# Panel.net
KiCad netlist of a schematic drawn in EAGLE
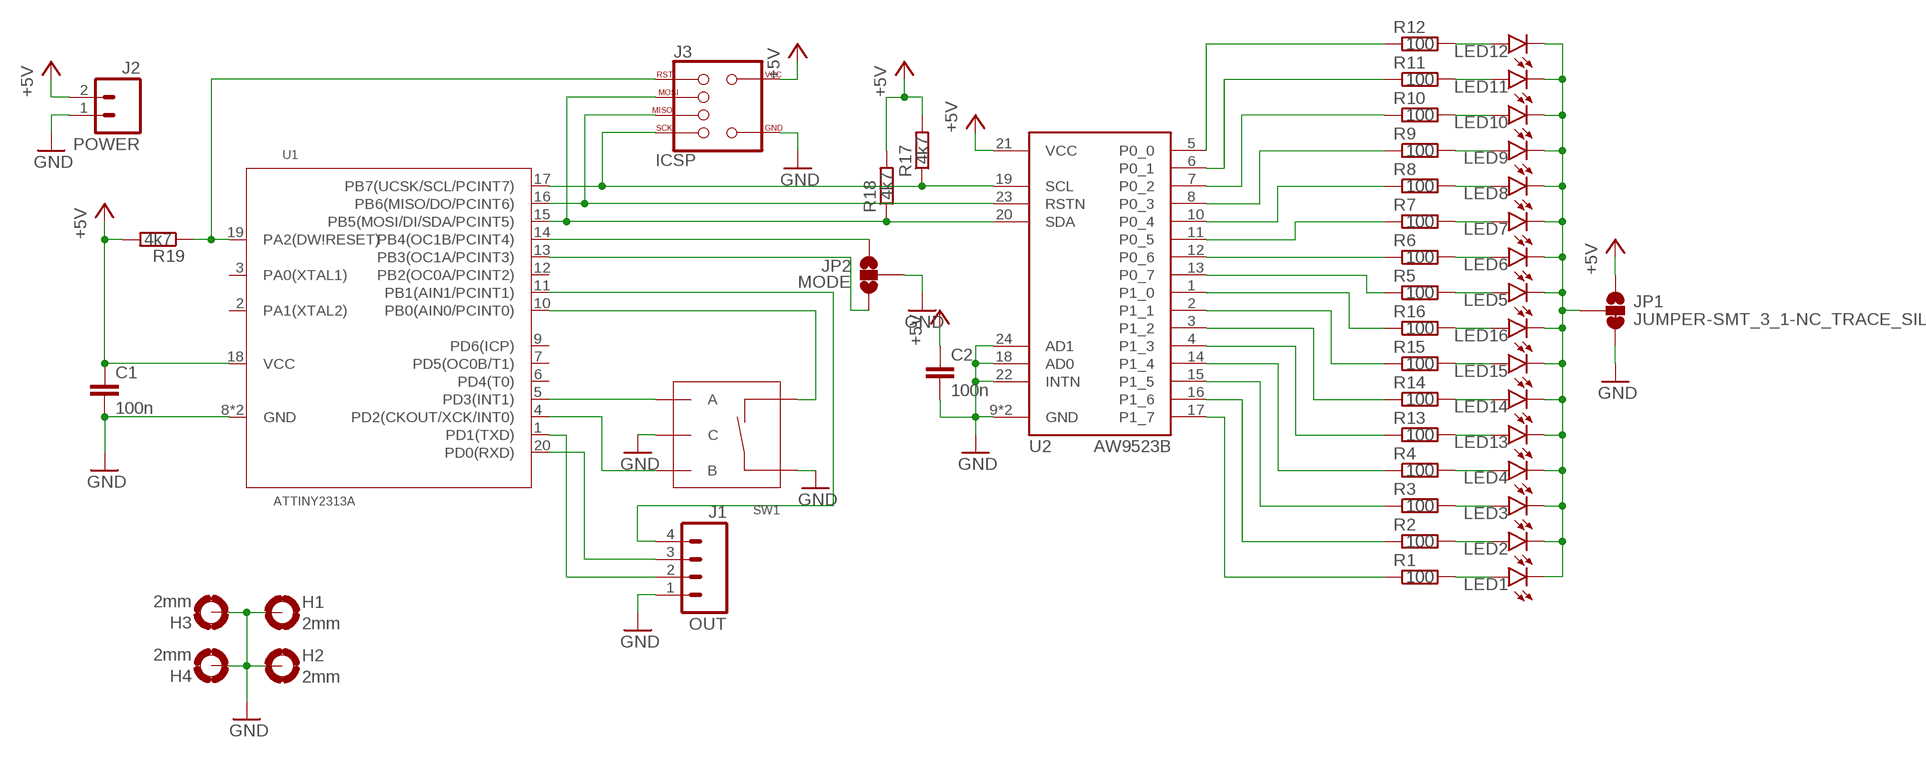
[diagram p0: schematic, sheet 2]
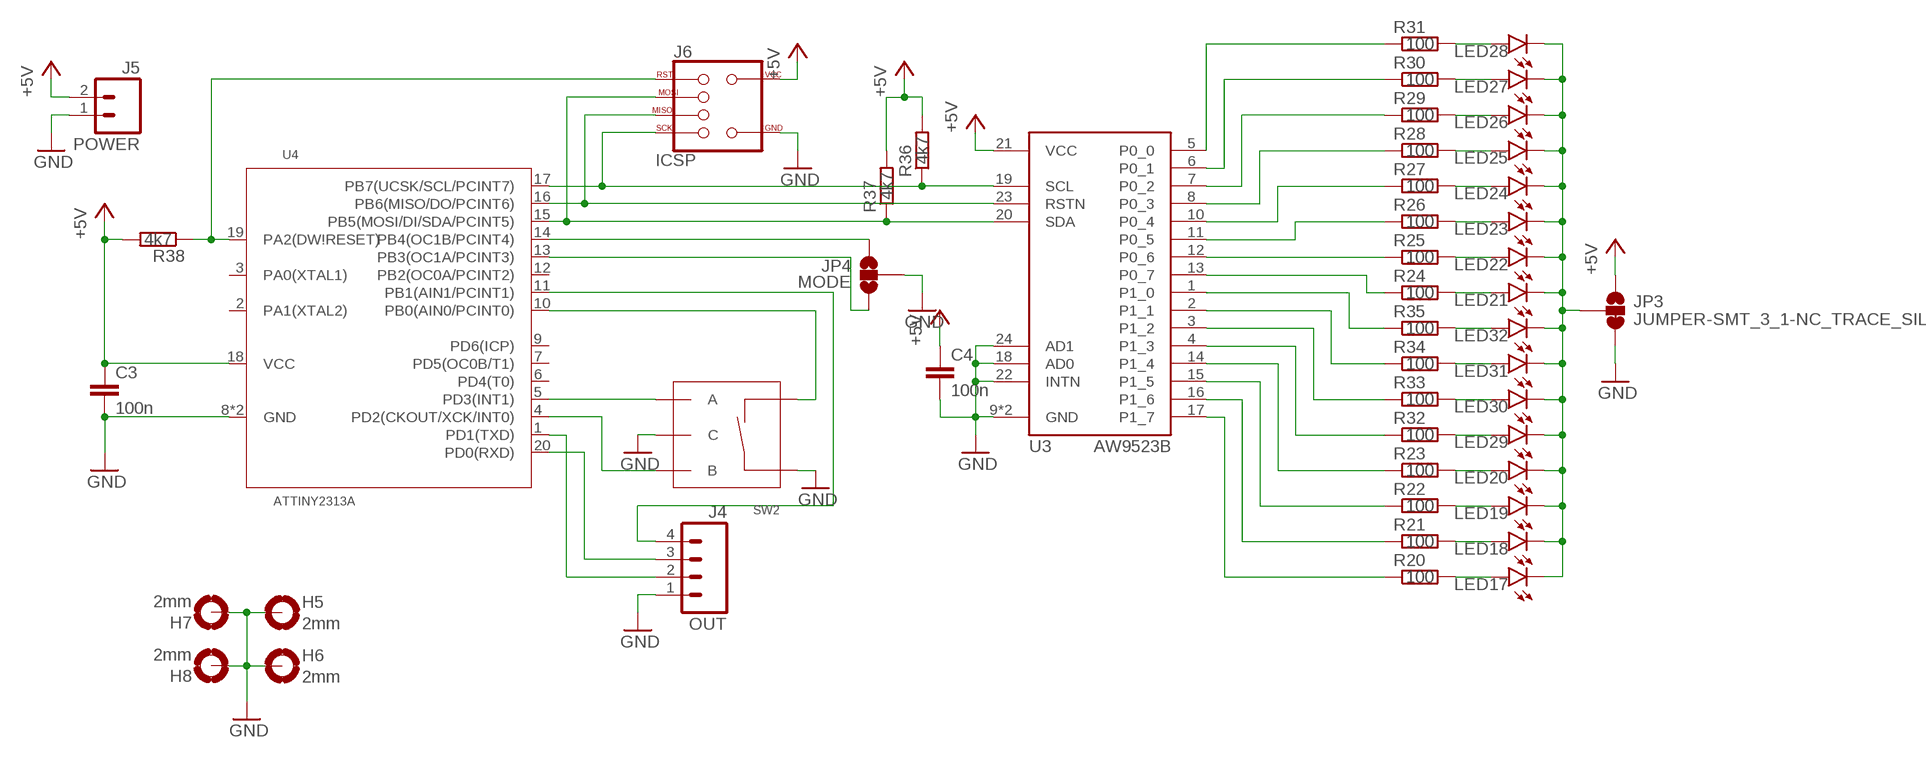
[diagram p1: schematic, sheet 3]

(export (version "E")
  (design (tool "Eeschema 10.0.6"))
  (components
    (comp (ref "C3")
      (value "100n")
      (footprint "eagle-import:C0402")
      (libsource (lib "eagle-import") (part "C-EUC0402"))
    )
    (comp (ref "C4")
      (value "100n")
      (footprint "eagle-import:C0402")
      (libsource (lib "eagle-import") (part "C-EUC0402"))
    )
    (comp (ref "H5")
      (value "2mm")
      (footprint "eagle-import:2,0-PAD")
      (libsource (lib "eagle-import") (part "MOUNT-PAD2MM"))
    )
    (comp (ref "H6")
      (value "2mm")
      (footprint "eagle-import:2,0-PAD")
      (libsource (lib "eagle-import") (part "MOUNT-PAD2MM"))
    )
    (comp (ref "H7")
      (value "2mm")
      (footprint "eagle-import:2,0-PAD")
      (libsource (lib "eagle-import") (part "MOUNT-PAD2MM"))
    )
    (comp (ref "H8")
      (value "2mm")
      (footprint "eagle-import:2,0-PAD")
      (libsource (lib "eagle-import") (part "MOUNT-PAD2MM"))
    )
    (comp (ref "J4")
      (value "OUT")
      (footprint "eagle-import:JST-4-PTH-VERT")
      (libsource (lib "eagle-import") (part "JST-XH4"))
    )
    (comp (ref "J5")
      (value "POWER")
      (footprint "eagle-import:JST-2-PTH-VERT")
      (libsource (lib "eagle-import") (part "JST-XH2"))
    )
    (comp (ref "J6")
      (value "ICSP")
      (footprint "eagle-import:MINI-ISP-LABELS")
      (libsource (lib "eagle-import") (part "MINI-ISP-LABELS"))
    )
    (comp (ref "JP3")
      (value "JUMPER-SMT_3_1-NC_TRACE_SILK")
      (footprint "eagle-import:SMT-JUMPER_3_1-NC_TRACE_SILK")
      (libsource (lib "eagle-import") (part "JUMPER-SMT_3_1-NC_TRACE_SILK"))
    )
    (comp (ref "JP4")
      (value "MODE")
      (footprint "eagle-import:SMT-JUMPER_3_NO_SILK")
      (libsource (lib "eagle-import") (part "JUMPER-SMT_3_NO_SILK"))
    )
    (comp (ref "LED17")
      (value "LED-BLUE0603")
      (footprint "eagle-import:0603-BLUE")
      (libsource (lib "eagle-import") (part "LED-BLUE0603"))
    )
    (comp (ref "LED18")
      (value "LED-BLUE0603")
      (footprint "eagle-import:0603-BLUE")
      (libsource (lib "eagle-import") (part "LED-BLUE0603"))
    )
    (comp (ref "LED19")
      (value "LED-BLUE0603")
      (footprint "eagle-import:0603-BLUE")
      (libsource (lib "eagle-import") (part "LED-BLUE0603"))
    )
    (comp (ref "LED20")
      (value "LED-BLUE0603")
      (footprint "eagle-import:0603-BLUE")
      (libsource (lib "eagle-import") (part "LED-BLUE0603"))
    )
    (comp (ref "LED21")
      (value "LED-BLUE0603")
      (footprint "eagle-import:0603-BLUE")
      (libsource (lib "eagle-import") (part "LED-BLUE0603"))
    )
    (comp (ref "LED22")
      (value "LED-BLUE0603")
      (footprint "eagle-import:0603-BLUE")
      (libsource (lib "eagle-import") (part "LED-BLUE0603"))
    )
    (comp (ref "LED23")
      (value "LED-BLUE0603")
      (footprint "eagle-import:0603-BLUE")
      (libsource (lib "eagle-import") (part "LED-BLUE0603"))
    )
    (comp (ref "LED24")
      (value "LED-BLUE0603")
      (footprint "eagle-import:0603-BLUE")
      (libsource (lib "eagle-import") (part "LED-BLUE0603"))
    )
    (comp (ref "LED25")
      (value "LED-BLUE0603")
      (footprint "eagle-import:0603-BLUE")
      (libsource (lib "eagle-import") (part "LED-BLUE0603"))
    )
    (comp (ref "LED26")
      (value "LED-BLUE0603")
      (footprint "eagle-import:0603-BLUE")
      (libsource (lib "eagle-import") (part "LED-BLUE0603"))
    )
    (comp (ref "LED27")
      (value "LED-BLUE0603")
      (footprint "eagle-import:0603-BLUE")
      (libsource (lib "eagle-import") (part "LED-BLUE0603"))
    )
    (comp (ref "LED28")
      (value "LED-BLUE0603")
      (footprint "eagle-import:0603-BLUE")
      (libsource (lib "eagle-import") (part "LED-BLUE0603"))
    )
    (comp (ref "LED29")
      (value "LED-BLUE0603")
      (footprint "eagle-import:0603-BLUE")
      (libsource (lib "eagle-import") (part "LED-BLUE0603"))
    )
    (comp (ref "LED30")
      (value "LED-BLUE0603")
      (footprint "eagle-import:0603-BLUE")
      (libsource (lib "eagle-import") (part "LED-BLUE0603"))
    )
    (comp (ref "LED31")
      (value "LED-BLUE0603")
      (footprint "eagle-import:0603-BLUE")
      (libsource (lib "eagle-import") (part "LED-BLUE0603"))
    )
    (comp (ref "LED32")
      (value "LED-BLUE0603")
      (footprint "eagle-import:0603-BLUE")
      (libsource (lib "eagle-import") (part "LED-BLUE0603"))
    )
    (comp (ref "R20")
      (value "100")
      (footprint "eagle-import:R0402")
      (libsource (lib "eagle-import") (part "R-EU_R0402"))
    )
    (comp (ref "R21")
      (value "100")
      (footprint "eagle-import:R0402")
      (libsource (lib "eagle-import") (part "R-EU_R0402"))
    )
    (comp (ref "R22")
      (value "100")
      (footprint "eagle-import:R0402")
      (libsource (lib "eagle-import") (part "R-EU_R0402"))
    )
    (comp (ref "R23")
      (value "100")
      (footprint "eagle-import:R0402")
      (libsource (lib "eagle-import") (part "R-EU_R0402"))
    )
    (comp (ref "R24")
      (value "100")
      (footprint "eagle-import:R0402")
      (libsource (lib "eagle-import") (part "R-EU_R0402"))
    )
    (comp (ref "R25")
      (value "100")
      (footprint "eagle-import:R0402")
      (libsource (lib "eagle-import") (part "R-EU_R0402"))
    )
    (comp (ref "R26")
      (value "100")
      (footprint "eagle-import:R0402")
      (libsource (lib "eagle-import") (part "R-EU_R0402"))
    )
    (comp (ref "R27")
      (value "100")
      (footprint "eagle-import:R0402")
      (libsource (lib "eagle-import") (part "R-EU_R0402"))
    )
    (comp (ref "R28")
      (value "100")
      (footprint "eagle-import:R0402")
      (libsource (lib "eagle-import") (part "R-EU_R0402"))
    )
    (comp (ref "R29")
      (value "100")
      (footprint "eagle-import:R0402")
      (libsource (lib "eagle-import") (part "R-EU_R0402"))
    )
    (comp (ref "R30")
      (value "100")
      (footprint "eagle-import:R0402")
      (libsource (lib "eagle-import") (part "R-EU_R0402"))
    )
    (comp (ref "R31")
      (value "100")
      (footprint "eagle-import:R0402")
      (libsource (lib "eagle-import") (part "R-EU_R0402"))
    )
    (comp (ref "R32")
      (value "100")
      (footprint "eagle-import:R0402")
      (libsource (lib "eagle-import") (part "R-EU_R0402"))
    )
    (comp (ref "R33")
      (value "100")
      (footprint "eagle-import:R0402")
      (libsource (lib "eagle-import") (part "R-EU_R0402"))
    )
    (comp (ref "R34")
      (value "100")
      (footprint "eagle-import:R0402")
      (libsource (lib "eagle-import") (part "R-EU_R0402"))
    )
    (comp (ref "R35")
      (value "100")
      (footprint "eagle-import:R0402")
      (libsource (lib "eagle-import") (part "R-EU_R0402"))
    )
    (comp (ref "R36")
      (value "4k7")
      (footprint "eagle-import:R0402")
      (libsource (lib "eagle-import") (part "R-EU_R0402"))
    )
    (comp (ref "R37")
      (value "4k7")
      (footprint "eagle-import:R0402")
      (libsource (lib "eagle-import") (part "R-EU_R0402"))
    )
    (comp (ref "R38")
      (value "4k7")
      (footprint "eagle-import:R0402")
      (libsource (lib "eagle-import") (part "R-EU_R0402"))
    )
    (comp (ref "SW2")
      (value "ROTARTY_ENCODER")
      (footprint "eagle-import:ROTARY_ENC_PLAIN")
      (libsource (lib "eagle-import") (part "ROTARTY_ENCODER"))
    )
    (comp (ref "U3")
      (value "AW9523B")
      (footprint "eagle-import:QFN50P400X400X80-25T270N")
      (libsource (lib "eagle-import") (part "AW9523B"))
    )
    (comp (ref "U4")
      (value "ATTINY2313A")
      (footprint "eagle-import:QFN50P400X400X80-21T260N")
      (libsource (lib "eagle-import") (part "ATTINY2313A"))
    )
    (comp (ref "C1")
      (value "100n")
      (footprint "eagle-import:C0402")
      (libsource (lib "eagle-import") (part "C-EUC0402"))
    )
    (comp (ref "C2")
      (value "100n")
      (footprint "eagle-import:C0402")
      (libsource (lib "eagle-import") (part "C-EUC0402"))
    )
    (comp (ref "H1")
      (value "2mm")
      (footprint "eagle-import:2,0-PAD")
      (libsource (lib "eagle-import") (part "MOUNT-PAD2MM"))
    )
    (comp (ref "H2")
      (value "2mm")
      (footprint "eagle-import:2,0-PAD")
      (libsource (lib "eagle-import") (part "MOUNT-PAD2MM"))
    )
    (comp (ref "H3")
      (value "2mm")
      (footprint "eagle-import:2,0-PAD")
      (libsource (lib "eagle-import") (part "MOUNT-PAD2MM"))
    )
    (comp (ref "H4")
      (value "2mm")
      (footprint "eagle-import:2,0-PAD")
      (libsource (lib "eagle-import") (part "MOUNT-PAD2MM"))
    )
    (comp (ref "J1")
      (value "OUT")
      (footprint "eagle-import:JST-4-PTH-VERT")
      (libsource (lib "eagle-import") (part "JST-XH4"))
    )
    (comp (ref "J2")
      (value "POWER")
      (footprint "eagle-import:JST-2-PTH-VERT")
      (libsource (lib "eagle-import") (part "JST-XH2"))
    )
    (comp (ref "J3")
      (value "ICSP")
      (footprint "eagle-import:MINI-ISP-LABELS")
      (libsource (lib "eagle-import") (part "MINI-ISP-LABELS"))
    )
    (comp (ref "JP1")
      (value "JUMPER-SMT_3_1-NC_TRACE_SILK")
      (footprint "eagle-import:SMT-JUMPER_3_1-NC_TRACE_SILK")
      (libsource (lib "eagle-import") (part "JUMPER-SMT_3_1-NC_TRACE_SILK"))
    )
    (comp (ref "JP2")
      (value "MODE")
      (footprint "eagle-import:SMT-JUMPER_3_NO_SILK")
      (libsource (lib "eagle-import") (part "JUMPER-SMT_3_NO_SILK"))
    )
    (comp (ref "LED1")
      (value "LED-BLUE0603")
      (footprint "eagle-import:0603-BLUE")
      (libsource (lib "eagle-import") (part "LED-BLUE0603"))
    )
    (comp (ref "LED2")
      (value "LED-BLUE0603")
      (footprint "eagle-import:0603-BLUE")
      (libsource (lib "eagle-import") (part "LED-BLUE0603"))
    )
    (comp (ref "LED3")
      (value "LED-BLUE0603")
      (footprint "eagle-import:0603-BLUE")
      (libsource (lib "eagle-import") (part "LED-BLUE0603"))
    )
    (comp (ref "LED4")
      (value "LED-BLUE0603")
      (footprint "eagle-import:0603-BLUE")
      (libsource (lib "eagle-import") (part "LED-BLUE0603"))
    )
    (comp (ref "LED5")
      (value "LED-BLUE0603")
      (footprint "eagle-import:0603-BLUE")
      (libsource (lib "eagle-import") (part "LED-BLUE0603"))
    )
    (comp (ref "LED6")
      (value "LED-BLUE0603")
      (footprint "eagle-import:0603-BLUE")
      (libsource (lib "eagle-import") (part "LED-BLUE0603"))
    )
    (comp (ref "LED7")
      (value "LED-BLUE0603")
      (footprint "eagle-import:0603-BLUE")
      (libsource (lib "eagle-import") (part "LED-BLUE0603"))
    )
    (comp (ref "LED8")
      (value "LED-BLUE0603")
      (footprint "eagle-import:0603-BLUE")
      (libsource (lib "eagle-import") (part "LED-BLUE0603"))
    )
    (comp (ref "LED9")
      (value "LED-BLUE0603")
      (footprint "eagle-import:0603-BLUE")
      (libsource (lib "eagle-import") (part "LED-BLUE0603"))
    )
    (comp (ref "LED10")
      (value "LED-BLUE0603")
      (footprint "eagle-import:0603-BLUE")
      (libsource (lib "eagle-import") (part "LED-BLUE0603"))
    )
    (comp (ref "LED11")
      (value "LED-BLUE0603")
      (footprint "eagle-import:0603-BLUE")
      (libsource (lib "eagle-import") (part "LED-BLUE0603"))
    )
    (comp (ref "LED12")
      (value "LED-BLUE0603")
      (footprint "eagle-import:0603-BLUE")
      (libsource (lib "eagle-import") (part "LED-BLUE0603"))
    )
    (comp (ref "LED13")
      (value "LED-BLUE0603")
      (footprint "eagle-import:0603-BLUE")
      (libsource (lib "eagle-import") (part "LED-BLUE0603"))
    )
    (comp (ref "LED14")
      (value "LED-BLUE0603")
      (footprint "eagle-import:0603-BLUE")
      (libsource (lib "eagle-import") (part "LED-BLUE0603"))
    )
    (comp (ref "LED15")
      (value "LED-BLUE0603")
      (footprint "eagle-import:0603-BLUE")
      (libsource (lib "eagle-import") (part "LED-BLUE0603"))
    )
    (comp (ref "LED16")
      (value "LED-BLUE0603")
      (footprint "eagle-import:0603-BLUE")
      (libsource (lib "eagle-import") (part "LED-BLUE0603"))
    )
    (comp (ref "R1")
      (value "100")
      (footprint "eagle-import:R0402")
      (libsource (lib "eagle-import") (part "R-EU_R0402"))
    )
    (comp (ref "R2")
      (value "100")
      (footprint "eagle-import:R0402")
      (libsource (lib "eagle-import") (part "R-EU_R0402"))
    )
    (comp (ref "R3")
      (value "100")
      (footprint "eagle-import:R0402")
      (libsource (lib "eagle-import") (part "R-EU_R0402"))
    )
    (comp (ref "R4")
      (value "100")
      (footprint "eagle-import:R0402")
      (libsource (lib "eagle-import") (part "R-EU_R0402"))
    )
    (comp (ref "R5")
      (value "100")
      (footprint "eagle-import:R0402")
      (libsource (lib "eagle-import") (part "R-EU_R0402"))
    )
    (comp (ref "R6")
      (value "100")
      (footprint "eagle-import:R0402")
      (libsource (lib "eagle-import") (part "R-EU_R0402"))
    )
    (comp (ref "R7")
      (value "100")
      (footprint "eagle-import:R0402")
      (libsource (lib "eagle-import") (part "R-EU_R0402"))
    )
    (comp (ref "R8")
      (value "100")
      (footprint "eagle-import:R0402")
      (libsource (lib "eagle-import") (part "R-EU_R0402"))
    )
    (comp (ref "R9")
      (value "100")
      (footprint "eagle-import:R0402")
      (libsource (lib "eagle-import") (part "R-EU_R0402"))
    )
    (comp (ref "R10")
      (value "100")
      (footprint "eagle-import:R0402")
      (libsource (lib "eagle-import") (part "R-EU_R0402"))
    )
    (comp (ref "R11")
      (value "100")
      (footprint "eagle-import:R0402")
      (libsource (lib "eagle-import") (part "R-EU_R0402"))
    )
    (comp (ref "R12")
      (value "100")
      (footprint "eagle-import:R0402")
      (libsource (lib "eagle-import") (part "R-EU_R0402"))
    )
    (comp (ref "R13")
      (value "100")
      (footprint "eagle-import:R0402")
      (libsource (lib "eagle-import") (part "R-EU_R0402"))
    )
    (comp (ref "R14")
      (value "100")
      (footprint "eagle-import:R0402")
      (libsource (lib "eagle-import") (part "R-EU_R0402"))
    )
    (comp (ref "R15")
      (value "100")
      (footprint "eagle-import:R0402")
      (libsource (lib "eagle-import") (part "R-EU_R0402"))
    )
    (comp (ref "R16")
      (value "100")
      (footprint "eagle-import:R0402")
      (libsource (lib "eagle-import") (part "R-EU_R0402"))
    )
    (comp (ref "R17")
      (value "4k7")
      (footprint "eagle-import:R0402")
      (libsource (lib "eagle-import") (part "R-EU_R0402"))
    )
    (comp (ref "R18")
      (value "4k7")
      (footprint "eagle-import:R0402")
      (libsource (lib "eagle-import") (part "R-EU_R0402"))
    )
    (comp (ref "R19")
      (value "4k7")
      (footprint "eagle-import:R0402")
      (libsource (lib "eagle-import") (part "R-EU_R0402"))
    )
    (comp (ref "SW1")
      (value "ROTARTY_ENCODER")
      (footprint "eagle-import:ROTARY_ENC_PLAIN")
      (libsource (lib "eagle-import") (part "ROTARTY_ENCODER"))
    )
    (comp (ref "U1")
      (value "ATTINY2313A")
      (footprint "eagle-import:QFN50P400X400X80-21T260N")
      (libsource (lib "eagle-import") (part "ATTINY2313A"))
    )
    (comp (ref "U2")
      (value "AW9523B")
      (footprint "eagle-import:QFN50P400X400X80-25T270N")
      (libsource (lib "eagle-import") (part "AW9523B"))
    )
  )
  (nets
    (net (code "1") (name "+5V") (class "Default")
      (node (ref "C1") (pin "1") (pinfunction "1_1") (pintype "passive"))
      (node (ref "C2") (pin "1") (pinfunction "1_1") (pintype "passive"))
      (node (ref "C3") (pin "1") (pinfunction "1_1") (pintype "passive"))
      (node (ref "C4") (pin "1") (pinfunction "1_1") (pintype "passive"))
      (node (ref "J2") (pin "2") (pinfunction "2_2") (pintype "passive"))
      (node (ref "J3") (pin "VDD") (pinfunction "2_VDD") (pintype "passive"))
      (node (ref "J5") (pin "2") (pinfunction "2_2") (pintype "passive"))
      (node (ref "J6") (pin "VDD") (pinfunction "2_VDD") (pintype "passive"))
      (node (ref "JP1") (pin "1") (pinfunction "1_1") (pintype "passive"))
      (node (ref "JP3") (pin "1") (pinfunction "1_1") (pintype "passive"))
      (node (ref "R17") (pin "2") (pinfunction "2_2") (pintype "passive"))
      (node (ref "R18") (pin "2") (pinfunction "2_2") (pintype "passive"))
      (node (ref "R19") (pin "2") (pinfunction "2_2") (pintype "passive"))
      (node (ref "R36") (pin "2") (pinfunction "2_2") (pintype "passive"))
      (node (ref "R37") (pin "2") (pinfunction "2_2") (pintype "passive"))
      (node (ref "R38") (pin "2") (pinfunction "2_2") (pintype "passive"))
      (node (ref "U1") (pin "18") (pinfunction "VCC_18") (pintype "power_in"))
      (node (ref "U2") (pin "21") (pinfunction "VCC_21") (pintype "power_in"))
      (node (ref "U3") (pin "21") (pinfunction "VCC_21") (pintype "power_in"))
      (node (ref "U4") (pin "18") (pinfunction "VCC_18") (pintype "power_in"))
    )
    (net (code "2") (name "GND") (class "Default")
      (node (ref "C1") (pin "2") (pinfunction "2_2") (pintype "passive"))
      (node (ref "C2") (pin "2") (pinfunction "2_2") (pintype "passive"))
      (node (ref "C3") (pin "2") (pinfunction "2_2") (pintype "passive"))
      (node (ref "C4") (pin "2") (pinfunction "2_2") (pintype "passive"))
      (node (ref "H1") (pin "B2,0") (pinfunction "MOUNT_B2,0") (pintype "passive"))
      (node (ref "H2") (pin "B2,0") (pinfunction "MOUNT_B2,0") (pintype "passive"))
      (node (ref "H3") (pin "B2,0") (pinfunction "MOUNT_B2,0") (pintype "passive"))
      (node (ref "H4") (pin "B2,0") (pinfunction "MOUNT_B2,0") (pintype "passive"))
      (node (ref "H5") (pin "B2,0") (pinfunction "MOUNT_B2,0") (pintype "passive"))
      (node (ref "H6") (pin "B2,0") (pinfunction "MOUNT_B2,0") (pintype "passive"))
      (node (ref "H7") (pin "B2,0") (pinfunction "MOUNT_B2,0") (pintype "passive"))
      (node (ref "H8") (pin "B2,0") (pinfunction "MOUNT_B2,0") (pintype "passive"))
      (node (ref "J1") (pin "1") (pinfunction "1_1") (pintype "passive"))
      (node (ref "J2") (pin "1") (pinfunction "1_1") (pintype "passive"))
      (node (ref "J3") (pin "GND") (pinfunction "6_GND") (pintype "passive"))
      (node (ref "J4") (pin "1") (pinfunction "1_1") (pintype "passive"))
      (node (ref "J5") (pin "1") (pinfunction "1_1") (pintype "passive"))
      (node (ref "J6") (pin "GND") (pinfunction "6_GND") (pintype "passive"))
      (node (ref "JP1") (pin "3") (pinfunction "3_3") (pintype "passive"))
      (node (ref "JP2") (pin "2") (pinfunction "2_2") (pintype "passive"))
      (node (ref "JP3") (pin "3") (pinfunction "3_3") (pintype "passive"))
      (node (ref "JP4") (pin "2") (pinfunction "2_2") (pintype "passive"))
      (node (ref "SW1") (pin "C") (pinfunction "C_C") (pintype "bidirectional"))
      (node (ref "SW1") (pin "SW+") (pinfunction "SW+_SW+") (pintype "bidirectional"))
      (node (ref "SW2") (pin "C") (pinfunction "C_C") (pintype "bidirectional"))
      (node (ref "SW2") (pin "SW+") (pinfunction "SW+_SW+") (pintype "bidirectional"))
      (node (ref "U1") (pin "21") (pinfunction "GND_21") (pintype "input"))
      (node (ref "U1") (pin "8") (pinfunction "GND_8") (pintype "input"))
      (node (ref "U2") (pin "18") (pinfunction "AD0_18") (pintype "input"))
      (node (ref "U2") (pin "22") (pinfunction "INTN_22") (pintype "output"))
      (node (ref "U2") (pin "24") (pinfunction "AD1_24") (pintype "input"))
      (node (ref "U2") (pin "25") (pinfunction "GND_25") (pintype "power_in"))
      (node (ref "U2") (pin "9") (pinfunction "GND_9") (pintype "power_in"))
      (node (ref "U3") (pin "18") (pinfunction "AD0_18") (pintype "input"))
      (node (ref "U3") (pin "22") (pinfunction "INTN_22") (pintype "output"))
      (node (ref "U3") (pin "24") (pinfunction "AD1_24") (pintype "input"))
      (node (ref "U3") (pin "25") (pinfunction "GND_25") (pintype "power_in"))
      (node (ref "U3") (pin "9") (pinfunction "GND_9") (pintype "power_in"))
      (node (ref "U4") (pin "21") (pinfunction "GND_21") (pintype "input"))
      (node (ref "U4") (pin "8") (pinfunction "GND_8") (pintype "input"))
    )
    (net (code "3") (name "Net-(J3-1)") (class "Default")
      (node (ref "J3") (pin "MISO") (pinfunction "1_MISO") (pintype "passive"))
      (node (ref "U1") (pin "16") (pinfunction "PB6(MISO/DO/PCINT6)_16") (pintype "input"))
      (node (ref "U2") (pin "23") (pinfunction "RSTN_23") (pintype "input"))
    )
    (net (code "4") (name "Net-(J3-3)") (class "Default")
      (node (ref "J3") (pin "SCK") (pinfunction "3_SCK") (pintype "passive"))
      (node (ref "R17") (pin "1") (pinfunction "1_1") (pintype "passive"))
      (node (ref "U1") (pin "17") (pinfunction "PB7(UCSK/SCL/PCINT7)_17") (pintype "input"))
      (node (ref "U2") (pin "19") (pinfunction "SCL_19") (pintype "input"))
    )
    (net (code "5") (name "Net-(J3-4)") (class "Default")
      (node (ref "J3") (pin "MOSI") (pinfunction "4_MOSI") (pintype "passive"))
      (node (ref "R18") (pin "1") (pinfunction "1_1") (pintype "passive"))
      (node (ref "U1") (pin "15") (pinfunction "PB5(MOSI/DI/SDA/PCINT5)_15") (pintype "output"))
      (node (ref "U2") (pin "20") (pinfunction "SDA_20") (pintype "bidirectional"))
    )
    (net (code "6") (name "Net-(J3-5)") (class "Default")
      (node (ref "J3") (pin "RESET") (pinfunction "5_RESET") (pintype "passive"))
      (node (ref "R19") (pin "1") (pinfunction "1_1") (pintype "passive"))
      (node (ref "U1") (pin "19") (pinfunction "PA2(DW\\~{RESET})_19") (pintype "output"))
    )
    (net (code "7") (name "Net-(J6-1)") (class "Default")
      (node (ref "J6") (pin "MISO") (pinfunction "1_MISO") (pintype "passive"))
      (node (ref "U3") (pin "23") (pinfunction "RSTN_23") (pintype "input"))
      (node (ref "U4") (pin "16") (pinfunction "PB6(MISO/DO/PCINT6)_16") (pintype "input"))
    )
    (net (code "8") (name "Net-(J6-3)") (class "Default")
      (node (ref "J6") (pin "SCK") (pinfunction "3_SCK") (pintype "passive"))
      (node (ref "R36") (pin "1") (pinfunction "1_1") (pintype "passive"))
      (node (ref "U3") (pin "19") (pinfunction "SCL_19") (pintype "input"))
      (node (ref "U4") (pin "17") (pinfunction "PB7(UCSK/SCL/PCINT7)_17") (pintype "input"))
    )
    (net (code "9") (name "Net-(J6-4)") (class "Default")
      (node (ref "J6") (pin "MOSI") (pinfunction "4_MOSI") (pintype "passive"))
      (node (ref "R37") (pin "1") (pinfunction "1_1") (pintype "passive"))
      (node (ref "U3") (pin "20") (pinfunction "SDA_20") (pintype "bidirectional"))
      (node (ref "U4") (pin "15") (pinfunction "PB5(MOSI/DI/SDA/PCINT5)_15") (pintype "output"))
    )
    (net (code "10") (name "Net-(J6-5)") (class "Default")
      (node (ref "J6") (pin "RESET") (pinfunction "5_RESET") (pintype "passive"))
      (node (ref "R38") (pin "1") (pinfunction "1_1") (pintype "passive"))
      (node (ref "U4") (pin "19") (pinfunction "PA2(DW\\~{RESET})_19") (pintype "output"))
    )
    (net (code "11") (name "Net-(JP1-Pad2)") (class "Default")
      (node (ref "JP1") (pin "2") (pinfunction "2_2") (pintype "passive"))
      (node (ref "LED1") (pin "C") (pinfunction "C_C") (pintype "passive"))
      (node (ref "LED10") (pin "C") (pinfunction "C_C") (pintype "passive"))
      (node (ref "LED11") (pin "C") (pinfunction "C_C") (pintype "passive"))
      (node (ref "LED12") (pin "C") (pinfunction "C_C") (pintype "passive"))
      (node (ref "LED13") (pin "C") (pinfunction "C_C") (pintype "passive"))
      (node (ref "LED14") (pin "C") (pinfunction "C_C") (pintype "passive"))
      (node (ref "LED15") (pin "C") (pinfunction "C_C") (pintype "passive"))
      (node (ref "LED16") (pin "C") (pinfunction "C_C") (pintype "passive"))
      (node (ref "LED2") (pin "C") (pinfunction "C_C") (pintype "passive"))
      (node (ref "LED3") (pin "C") (pinfunction "C_C") (pintype "passive"))
      (node (ref "LED4") (pin "C") (pinfunction "C_C") (pintype "passive"))
      (node (ref "LED5") (pin "C") (pinfunction "C_C") (pintype "passive"))
      (node (ref "LED6") (pin "C") (pinfunction "C_C") (pintype "passive"))
      (node (ref "LED7") (pin "C") (pinfunction "C_C") (pintype "passive"))
      (node (ref "LED8") (pin "C") (pinfunction "C_C") (pintype "passive"))
      (node (ref "LED9") (pin "C") (pinfunction "C_C") (pintype "passive"))
    )
    (net (code "12") (name "Net-(JP3-Pad2)") (class "Default")
      (node (ref "JP3") (pin "2") (pinfunction "2_2") (pintype "passive"))
      (node (ref "LED17") (pin "C") (pinfunction "C_C") (pintype "passive"))
      (node (ref "LED18") (pin "C") (pinfunction "C_C") (pintype "passive"))
      (node (ref "LED19") (pin "C") (pinfunction "C_C") (pintype "passive"))
      (node (ref "LED20") (pin "C") (pinfunction "C_C") (pintype "passive"))
      (node (ref "LED21") (pin "C") (pinfunction "C_C") (pintype "passive"))
      (node (ref "LED22") (pin "C") (pinfunction "C_C") (pintype "passive"))
      (node (ref "LED23") (pin "C") (pinfunction "C_C") (pintype "passive"))
      (node (ref "LED24") (pin "C") (pinfunction "C_C") (pintype "passive"))
      (node (ref "LED25") (pin "C") (pinfunction "C_C") (pintype "passive"))
      (node (ref "LED26") (pin "C") (pinfunction "C_C") (pintype "passive"))
      (node (ref "LED27") (pin "C") (pinfunction "C_C") (pintype "passive"))
      (node (ref "LED28") (pin "C") (pinfunction "C_C") (pintype "passive"))
      (node (ref "LED29") (pin "C") (pinfunction "C_C") (pintype "passive"))
      (node (ref "LED30") (pin "C") (pinfunction "C_C") (pintype "passive"))
      (node (ref "LED31") (pin "C") (pinfunction "C_C") (pintype "passive"))
      (node (ref "LED32") (pin "C") (pinfunction "C_C") (pintype "passive"))
    )
    (net (code "13") (name "Net-(LED1-PadA)") (class "Default")
      (node (ref "LED1") (pin "A") (pinfunction "A_A") (pintype "passive"))
      (node (ref "R1") (pin "2") (pinfunction "2_2") (pintype "passive"))
    )
    (net (code "14") (name "Net-(LED2-PadA)") (class "Default")
      (node (ref "LED2") (pin "A") (pinfunction "A_A") (pintype "passive"))
      (node (ref "R2") (pin "2") (pinfunction "2_2") (pintype "passive"))
    )
    (net (code "15") (name "Net-(LED3-PadA)") (class "Default")
      (node (ref "LED3") (pin "A") (pinfunction "A_A") (pintype "passive"))
      (node (ref "R3") (pin "2") (pinfunction "2_2") (pintype "passive"))
    )
    (net (code "16") (name "Net-(LED4-PadA)") (class "Default")
      (node (ref "LED4") (pin "A") (pinfunction "A_A") (pintype "passive"))
      (node (ref "R4") (pin "2") (pinfunction "2_2") (pintype "passive"))
    )
    (net (code "17") (name "Net-(LED5-PadA)") (class "Default")
      (node (ref "LED5") (pin "A") (pinfunction "A_A") (pintype "passive"))
      (node (ref "R5") (pin "2") (pinfunction "2_2") (pintype "passive"))
    )
    (net (code "18") (name "Net-(LED6-PadA)") (class "Default")
      (node (ref "LED6") (pin "A") (pinfunction "A_A") (pintype "passive"))
      (node (ref "R6") (pin "2") (pinfunction "2_2") (pintype "passive"))
    )
    (net (code "19") (name "Net-(LED7-PadA)") (class "Default")
      (node (ref "LED7") (pin "A") (pinfunction "A_A") (pintype "passive"))
      (node (ref "R7") (pin "2") (pinfunction "2_2") (pintype "passive"))
    )
    (net (code "20") (name "Net-(LED8-PadA)") (class "Default")
      (node (ref "LED8") (pin "A") (pinfunction "A_A") (pintype "passive"))
      (node (ref "R8") (pin "2") (pinfunction "2_2") (pintype "passive"))
    )
    (net (code "21") (name "Net-(LED9-PadA)") (class "Default")
      (node (ref "LED9") (pin "A") (pinfunction "A_A") (pintype "passive"))
      (node (ref "R9") (pin "2") (pinfunction "2_2") (pintype "passive"))
    )
    (net (code "22") (name "Net-(LED10-PadA)") (class "Default")
      (node (ref "LED10") (pin "A") (pinfunction "A_A") (pintype "passive"))
      (node (ref "R10") (pin "2") (pinfunction "2_2") (pintype "passive"))
    )
    (net (code "23") (name "Net-(LED11-PadA)") (class "Default")
      (node (ref "LED11") (pin "A") (pinfunction "A_A") (pintype "passive"))
      (node (ref "R11") (pin "2") (pinfunction "2_2") (pintype "passive"))
    )
    (net (code "24") (name "Net-(LED12-PadA)") (class "Default")
      (node (ref "LED12") (pin "A") (pinfunction "A_A") (pintype "passive"))
      (node (ref "R12") (pin "2") (pinfunction "2_2") (pintype "passive"))
    )
    (net (code "25") (name "Net-(LED13-PadA)") (class "Default")
      (node (ref "LED13") (pin "A") (pinfunction "A_A") (pintype "passive"))
      (node (ref "R13") (pin "2") (pinfunction "2_2") (pintype "passive"))
    )
    (net (code "26") (name "Net-(LED14-PadA)") (class "Default")
      (node (ref "LED14") (pin "A") (pinfunction "A_A") (pintype "passive"))
      (node (ref "R14") (pin "2") (pinfunction "2_2") (pintype "passive"))
    )
    (net (code "27") (name "Net-(LED15-PadA)") (class "Default")
      (node (ref "LED15") (pin "A") (pinfunction "A_A") (pintype "passive"))
      (node (ref "R15") (pin "2") (pinfunction "2_2") (pintype "passive"))
    )
    (net (code "28") (name "Net-(LED16-PadA)") (class "Default")
      (node (ref "LED16") (pin "A") (pinfunction "A_A") (pintype "passive"))
      (node (ref "R16") (pin "2") (pinfunction "2_2") (pintype "passive"))
    )
    (net (code "29") (name "Net-(LED17-PadA)") (class "Default")
      (node (ref "LED17") (pin "A") (pinfunction "A_A") (pintype "passive"))
      (node (ref "R20") (pin "2") (pinfunction "2_2") (pintype "passive"))
    )
    (net (code "30") (name "Net-(LED18-PadA)") (class "Default")
      (node (ref "LED18") (pin "A") (pinfunction "A_A") (pintype "passive"))
      (node (ref "R21") (pin "2") (pinfunction "2_2") (pintype "passive"))
    )
    (net (code "31") (name "Net-(LED19-PadA)") (class "Default")
      (node (ref "LED19") (pin "A") (pinfunction "A_A") (pintype "passive"))
      (node (ref "R22") (pin "2") (pinfunction "2_2") (pintype "passive"))
    )
    (net (code "32") (name "Net-(LED20-PadA)") (class "Default")
      (node (ref "LED20") (pin "A") (pinfunction "A_A") (pintype "passive"))
      (node (ref "R23") (pin "2") (pinfunction "2_2") (pintype "passive"))
    )
    (net (code "33") (name "Net-(LED21-PadA)") (class "Default")
      (node (ref "LED21") (pin "A") (pinfunction "A_A") (pintype "passive"))
      (node (ref "R24") (pin "2") (pinfunction "2_2") (pintype "passive"))
    )
    (net (code "34") (name "Net-(LED22-PadA)") (class "Default")
      (node (ref "LED22") (pin "A") (pinfunction "A_A") (pintype "passive"))
      (node (ref "R25") (pin "2") (pinfunction "2_2") (pintype "passive"))
    )
    (net (code "35") (name "Net-(LED23-PadA)") (class "Default")
      (node (ref "LED23") (pin "A") (pinfunction "A_A") (pintype "passive"))
      (node (ref "R26") (pin "2") (pinfunction "2_2") (pintype "passive"))
    )
    (net (code "36") (name "Net-(LED24-PadA)") (class "Default")
      (node (ref "LED24") (pin "A") (pinfunction "A_A") (pintype "passive"))
      (node (ref "R27") (pin "2") (pinfunction "2_2") (pintype "passive"))
    )
    (net (code "37") (name "Net-(LED25-PadA)") (class "Default")
      (node (ref "LED25") (pin "A") (pinfunction "A_A") (pintype "passive"))
      (node (ref "R28") (pin "2") (pinfunction "2_2") (pintype "passive"))
    )
    (net (code "38") (name "Net-(LED26-PadA)") (class "Default")
      (node (ref "LED26") (pin "A") (pinfunction "A_A") (pintype "passive"))
      (node (ref "R29") (pin "2") (pinfunction "2_2") (pintype "passive"))
    )
    (net (code "39") (name "Net-(LED27-PadA)") (class "Default")
      (node (ref "LED27") (pin "A") (pinfunction "A_A") (pintype "passive"))
      (node (ref "R30") (pin "2") (pinfunction "2_2") (pintype "passive"))
    )
    (net (code "40") (name "Net-(LED28-PadA)") (class "Default")
      (node (ref "LED28") (pin "A") (pinfunction "A_A") (pintype "passive"))
      (node (ref "R31") (pin "2") (pinfunction "2_2") (pintype "passive"))
    )
    (net (code "41") (name "Net-(LED29-PadA)") (class "Default")
      (node (ref "LED29") (pin "A") (pinfunction "A_A") (pintype "passive"))
      (node (ref "R32") (pin "2") (pinfunction "2_2") (pintype "passive"))
    )
    (net (code "42") (name "Net-(LED30-PadA)") (class "Default")
      (node (ref "LED30") (pin "A") (pinfunction "A_A") (pintype "passive"))
      (node (ref "R33") (pin "2") (pinfunction "2_2") (pintype "passive"))
    )
    (net (code "43") (name "Net-(LED31-PadA)") (class "Default")
      (node (ref "LED31") (pin "A") (pinfunction "A_A") (pintype "passive"))
      (node (ref "R34") (pin "2") (pinfunction "2_2") (pintype "passive"))
    )
    (net (code "44") (name "Net-(LED32-PadA)") (class "Default")
      (node (ref "LED32") (pin "A") (pinfunction "A_A") (pintype "passive"))
      (node (ref "R35") (pin "2") (pinfunction "2_2") (pintype "passive"))
    )
    (net (code "45") (name "Net-(U1-PB0(AIN0{slash}PCINT0))") (class "Default")
      (node (ref "SW1") (pin "SW-") (pinfunction "SW-_SW-") (pintype "bidirectional"))
      (node (ref "U1") (pin "10") (pinfunction "PB0(AIN0/PCINT0)_10") (pintype "output"))
    )
    (net (code "46") (name "Net-(U1-PB1(AIN1{slash}PCINT1))") (class "Default")
      (node (ref "J1") (pin "4") (pinfunction "4_4") (pintype "passive"))
      (node (ref "U1") (pin "11") (pinfunction "PB1(AIN1/PCINT1)_11") (pintype "output"))
    )
    (net (code "47") (name "Net-(U1-PB3(OC1A{slash}PCINT3))") (class "Default")
      (node (ref "JP2") (pin "3") (pinfunction "3_3") (pintype "passive"))
      (node (ref "U1") (pin "13") (pinfunction "PB3(OC1A/PCINT3)_13") (pintype "input"))
    )
    (net (code "48") (name "Net-(U1-PB4(OC1B{slash}PCINT4))") (class "Default")
      (node (ref "JP2") (pin "1") (pinfunction "1_1") (pintype "passive"))
      (node (ref "U1") (pin "14") (pinfunction "PB4(OC1B/PCINT4)_14") (pintype "input"))
    )
    (net (code "49") (name "Net-(U1-PD0(RXD))") (class "Default")
      (node (ref "J1") (pin "3") (pinfunction "3_3") (pintype "passive"))
      (node (ref "U1") (pin "20") (pinfunction "PD0(RXD)_20") (pintype "input"))
    )
    (net (code "50") (name "Net-(U1-PD1(TXD))") (class "Default")
      (node (ref "J1") (pin "2") (pinfunction "2_2") (pintype "passive"))
      (node (ref "U1") (pin "1") (pinfunction "PD1(TXD)_1") (pintype "output"))
    )
    (net (code "51") (name "Net-(U1-PD2(CKOUT{slash}XCK{slash}INT0))") (class "Default")
      (node (ref "SW1") (pin "B") (pinfunction "B_B") (pintype "bidirectional"))
      (node (ref "U1") (pin "4") (pinfunction "PD2(CKOUT/XCK/INT0)_4") (pintype "input"))
    )
    (net (code "52") (name "Net-(U1-PD3(INT1))") (class "Default")
      (node (ref "SW1") (pin "A") (pinfunction "A_A") (pintype "bidirectional"))
      (node (ref "U1") (pin "5") (pinfunction "PD3(INT1)_5") (pintype "output"))
    )
    (net (code "53") (name "Net-(U2-P0_0)") (class "Default")
      (node (ref "R12") (pin "1") (pinfunction "1_1") (pintype "passive"))
      (node (ref "U2") (pin "5") (pinfunction "P0_0_5") (pintype "bidirectional"))
    )
    (net (code "54") (name "Net-(U2-P0_1)") (class "Default")
      (node (ref "R11") (pin "1") (pinfunction "1_1") (pintype "passive"))
      (node (ref "U2") (pin "6") (pinfunction "P0_1_6") (pintype "bidirectional"))
    )
    (net (code "55") (name "Net-(U2-P0_2)") (class "Default")
      (node (ref "R10") (pin "1") (pinfunction "1_1") (pintype "passive"))
      (node (ref "U2") (pin "7") (pinfunction "P0_2_7") (pintype "bidirectional"))
    )
    (net (code "56") (name "Net-(U2-P0_3)") (class "Default")
      (node (ref "R9") (pin "1") (pinfunction "1_1") (pintype "passive"))
      (node (ref "U2") (pin "8") (pinfunction "P0_3_8") (pintype "bidirectional"))
    )
    (net (code "57") (name "Net-(U2-P0_4)") (class "Default")
      (node (ref "R8") (pin "1") (pinfunction "1_1") (pintype "passive"))
      (node (ref "U2") (pin "10") (pinfunction "P0_4_10") (pintype "bidirectional"))
    )
    (net (code "58") (name "Net-(U2-P0_5)") (class "Default")
      (node (ref "R7") (pin "1") (pinfunction "1_1") (pintype "passive"))
      (node (ref "U2") (pin "11") (pinfunction "P0_5_11") (pintype "bidirectional"))
    )
    (net (code "59") (name "Net-(U2-P0_6)") (class "Default")
      (node (ref "R6") (pin "1") (pinfunction "1_1") (pintype "passive"))
      (node (ref "U2") (pin "12") (pinfunction "P0_6_12") (pintype "bidirectional"))
    )
    (net (code "60") (name "Net-(U2-P0_7)") (class "Default")
      (node (ref "R5") (pin "1") (pinfunction "1_1") (pintype "passive"))
      (node (ref "U2") (pin "13") (pinfunction "P0_7_13") (pintype "bidirectional"))
    )
    (net (code "61") (name "Net-(U2-P1_0)") (class "Default")
      (node (ref "R16") (pin "1") (pinfunction "1_1") (pintype "passive"))
      (node (ref "U2") (pin "1") (pinfunction "P1_0_1") (pintype "bidirectional"))
    )
    (net (code "62") (name "Net-(U2-P1_1)") (class "Default")
      (node (ref "R15") (pin "1") (pinfunction "1_1") (pintype "passive"))
      (node (ref "U2") (pin "2") (pinfunction "P1_1_2") (pintype "bidirectional"))
    )
    (net (code "63") (name "Net-(U2-P1_2)") (class "Default")
      (node (ref "R14") (pin "1") (pinfunction "1_1") (pintype "passive"))
      (node (ref "U2") (pin "3") (pinfunction "P1_2_3") (pintype "bidirectional"))
    )
    (net (code "64") (name "Net-(U2-P1_3)") (class "Default")
      (node (ref "R13") (pin "1") (pinfunction "1_1") (pintype "passive"))
      (node (ref "U2") (pin "4") (pinfunction "P1_3_4") (pintype "bidirectional"))
    )
    (net (code "65") (name "Net-(U2-P1_4)") (class "Default")
      (node (ref "R4") (pin "1") (pinfunction "1_1") (pintype "passive"))
      (node (ref "U2") (pin "14") (pinfunction "P1_4_14") (pintype "bidirectional"))
    )
    (net (code "66") (name "Net-(U2-P1_5)") (class "Default")
      (node (ref "R3") (pin "1") (pinfunction "1_1") (pintype "passive"))
      (node (ref "U2") (pin "15") (pinfunction "P1_5_15") (pintype "bidirectional"))
    )
    (net (code "67") (name "Net-(U2-P1_6)") (class "Default")
      (node (ref "R2") (pin "1") (pinfunction "1_1") (pintype "passive"))
      (node (ref "U2") (pin "16") (pinfunction "P1_6_16") (pintype "bidirectional"))
    )
    (net (code "68") (name "Net-(U2-P1_7)") (class "Default")
      (node (ref "R1") (pin "1") (pinfunction "1_1") (pintype "passive"))
      (node (ref "U2") (pin "17") (pinfunction "P1_7_17") (pintype "bidirectional"))
    )
    (net (code "69") (name "Net-(U3-P0_0)") (class "Default")
      (node (ref "R31") (pin "1") (pinfunction "1_1") (pintype "passive"))
      (node (ref "U3") (pin "5") (pinfunction "P0_0_5") (pintype "bidirectional"))
    )
    (net (code "70") (name "Net-(U3-P0_1)") (class "Default")
      (node (ref "R30") (pin "1") (pinfunction "1_1") (pintype "passive"))
      (node (ref "U3") (pin "6") (pinfunction "P0_1_6") (pintype "bidirectional"))
    )
    (net (code "71") (name "Net-(U3-P0_2)") (class "Default")
      (node (ref "R29") (pin "1") (pinfunction "1_1") (pintype "passive"))
      (node (ref "U3") (pin "7") (pinfunction "P0_2_7") (pintype "bidirectional"))
    )
    (net (code "72") (name "Net-(U3-P0_3)") (class "Default")
      (node (ref "R28") (pin "1") (pinfunction "1_1") (pintype "passive"))
      (node (ref "U3") (pin "8") (pinfunction "P0_3_8") (pintype "bidirectional"))
    )
    (net (code "73") (name "Net-(U3-P0_4)") (class "Default")
      (node (ref "R27") (pin "1") (pinfunction "1_1") (pintype "passive"))
      (node (ref "U3") (pin "10") (pinfunction "P0_4_10") (pintype "bidirectional"))
    )
    (net (code "74") (name "Net-(U3-P0_5)") (class "Default")
      (node (ref "R26") (pin "1") (pinfunction "1_1") (pintype "passive"))
      (node (ref "U3") (pin "11") (pinfunction "P0_5_11") (pintype "bidirectional"))
    )
    (net (code "75") (name "Net-(U3-P0_6)") (class "Default")
      (node (ref "R25") (pin "1") (pinfunction "1_1") (pintype "passive"))
      (node (ref "U3") (pin "12") (pinfunction "P0_6_12") (pintype "bidirectional"))
    )
    (net (code "76") (name "Net-(U3-P0_7)") (class "Default")
      (node (ref "R24") (pin "1") (pinfunction "1_1") (pintype "passive"))
      (node (ref "U3") (pin "13") (pinfunction "P0_7_13") (pintype "bidirectional"))
    )
    (net (code "77") (name "Net-(U3-P1_0)") (class "Default")
      (node (ref "R35") (pin "1") (pinfunction "1_1") (pintype "passive"))
      (node (ref "U3") (pin "1") (pinfunction "P1_0_1") (pintype "bidirectional"))
    )
    (net (code "78") (name "Net-(U3-P1_1)") (class "Default")
      (node (ref "R34") (pin "1") (pinfunction "1_1") (pintype "passive"))
      (node (ref "U3") (pin "2") (pinfunction "P1_1_2") (pintype "bidirectional"))
    )
    (net (code "79") (name "Net-(U3-P1_2)") (class "Default")
      (node (ref "R33") (pin "1") (pinfunction "1_1") (pintype "passive"))
      (node (ref "U3") (pin "3") (pinfunction "P1_2_3") (pintype "bidirectional"))
    )
    (net (code "80") (name "Net-(U3-P1_3)") (class "Default")
      (node (ref "R32") (pin "1") (pinfunction "1_1") (pintype "passive"))
      (node (ref "U3") (pin "4") (pinfunction "P1_3_4") (pintype "bidirectional"))
    )
    (net (code "81") (name "Net-(U3-P1_4)") (class "Default")
      (node (ref "R23") (pin "1") (pinfunction "1_1") (pintype "passive"))
      (node (ref "U3") (pin "14") (pinfunction "P1_4_14") (pintype "bidirectional"))
    )
    (net (code "82") (name "Net-(U3-P1_5)") (class "Default")
      (node (ref "R22") (pin "1") (pinfunction "1_1") (pintype "passive"))
      (node (ref "U3") (pin "15") (pinfunction "P1_5_15") (pintype "bidirectional"))
    )
    (net (code "83") (name "Net-(U3-P1_6)") (class "Default")
      (node (ref "R21") (pin "1") (pinfunction "1_1") (pintype "passive"))
      (node (ref "U3") (pin "16") (pinfunction "P1_6_16") (pintype "bidirectional"))
    )
    (net (code "84") (name "Net-(U3-P1_7)") (class "Default")
      (node (ref "R20") (pin "1") (pinfunction "1_1") (pintype "passive"))
      (node (ref "U3") (pin "17") (pinfunction "P1_7_17") (pintype "bidirectional"))
    )
    (net (code "85") (name "Net-(U4-PB0(AIN0{slash}PCINT0))") (class "Default")
      (node (ref "SW2") (pin "SW-") (pinfunction "SW-_SW-") (pintype "bidirectional"))
      (node (ref "U4") (pin "10") (pinfunction "PB0(AIN0/PCINT0)_10") (pintype "output"))
    )
    (net (code "86") (name "Net-(U4-PB1(AIN1{slash}PCINT1))") (class "Default")
      (node (ref "J4") (pin "4") (pinfunction "4_4") (pintype "passive"))
      (node (ref "U4") (pin "11") (pinfunction "PB1(AIN1/PCINT1)_11") (pintype "output"))
    )
    (net (code "87") (name "Net-(U4-PB3(OC1A{slash}PCINT3))") (class "Default")
      (node (ref "JP4") (pin "3") (pinfunction "3_3") (pintype "passive"))
      (node (ref "U4") (pin "13") (pinfunction "PB3(OC1A/PCINT3)_13") (pintype "input"))
    )
    (net (code "88") (name "Net-(U4-PB4(OC1B{slash}PCINT4))") (class "Default")
      (node (ref "JP4") (pin "1") (pinfunction "1_1") (pintype "passive"))
      (node (ref "U4") (pin "14") (pinfunction "PB4(OC1B/PCINT4)_14") (pintype "input"))
    )
    (net (code "89") (name "Net-(U4-PD0(RXD))") (class "Default")
      (node (ref "J4") (pin "3") (pinfunction "3_3") (pintype "passive"))
      (node (ref "U4") (pin "20") (pinfunction "PD0(RXD)_20") (pintype "input"))
    )
    (net (code "90") (name "Net-(U4-PD1(TXD))") (class "Default")
      (node (ref "J4") (pin "2") (pinfunction "2_2") (pintype "passive"))
      (node (ref "U4") (pin "1") (pinfunction "PD1(TXD)_1") (pintype "output"))
    )
    (net (code "91") (name "Net-(U4-PD2(CKOUT{slash}XCK{slash}INT0))") (class "Default")
      (node (ref "SW2") (pin "B") (pinfunction "B_B") (pintype "bidirectional"))
      (node (ref "U4") (pin "4") (pinfunction "PD2(CKOUT/XCK/INT0)_4") (pintype "input"))
    )
    (net (code "92") (name "Net-(U4-PD3(INT1))") (class "Default")
      (node (ref "SW2") (pin "A") (pinfunction "A_A") (pintype "bidirectional"))
      (node (ref "U4") (pin "5") (pinfunction "PD3(INT1)_5") (pintype "output"))
    )
    (net (code "93") (name "unconnected-(U1-PA0(XTAL1)-Pad3)") (class "Default")
      (node (ref "U1") (pin "3") (pinfunction "PA0(XTAL1)_3") (pintype "input"))
    )
    (net (code "94") (name "unconnected-(U1-PA1(XTAL2)-Pad2)") (class "Default")
      (node (ref "U1") (pin "2") (pinfunction "PA1(XTAL2)_2") (pintype "input"))
    )
    (net (code "95") (name "unconnected-(U1-PB2(OC0A{slash}PCINT2)-Pad12)") (class "Default")
      (node (ref "U1") (pin "12") (pinfunction "PB2(OC0A/PCINT2)_12") (pintype "output"))
    )
    (net (code "96") (name "unconnected-(U1-PD4(T0)-Pad6)") (class "Default")
      (node (ref "U1") (pin "6") (pinfunction "PD4(T0)_6") (pintype "input"))
    )
    (net (code "97") (name "unconnected-(U1-PD5(OC0B{slash}T1)-Pad7)") (class "Default")
      (node (ref "U1") (pin "7") (pinfunction "PD5(OC0B/T1)_7") (pintype "input"))
    )
    (net (code "98") (name "unconnected-(U1-PD6(ICP)-Pad9)") (class "Default")
      (node (ref "U1") (pin "9") (pinfunction "PD6(ICP)_9") (pintype "output"))
    )
    (net (code "99") (name "unconnected-(U4-PA0(XTAL1)-Pad3)") (class "Default")
      (node (ref "U4") (pin "3") (pinfunction "PA0(XTAL1)_3") (pintype "input"))
    )
    (net (code "100") (name "unconnected-(U4-PA1(XTAL2)-Pad2)") (class "Default")
      (node (ref "U4") (pin "2") (pinfunction "PA1(XTAL2)_2") (pintype "input"))
    )
    (net (code "101") (name "unconnected-(U4-PB2(OC0A{slash}PCINT2)-Pad12)") (class "Default")
      (node (ref "U4") (pin "12") (pinfunction "PB2(OC0A/PCINT2)_12") (pintype "output"))
    )
    (net (code "102") (name "unconnected-(U4-PD4(T0)-Pad6)") (class "Default")
      (node (ref "U4") (pin "6") (pinfunction "PD4(T0)_6") (pintype "input"))
    )
    (net (code "103") (name "unconnected-(U4-PD5(OC0B{slash}T1)-Pad7)") (class "Default")
      (node (ref "U4") (pin "7") (pinfunction "PD5(OC0B/T1)_7") (pintype "input"))
    )
    (net (code "104") (name "unconnected-(U4-PD6(ICP)-Pad9)") (class "Default")
      (node (ref "U4") (pin "9") (pinfunction "PD6(ICP)_9") (pintype "output"))
    )
  )
)
